# jellyFish_schematic.net
KiCad netlist of a schematic drawn in EAGLE
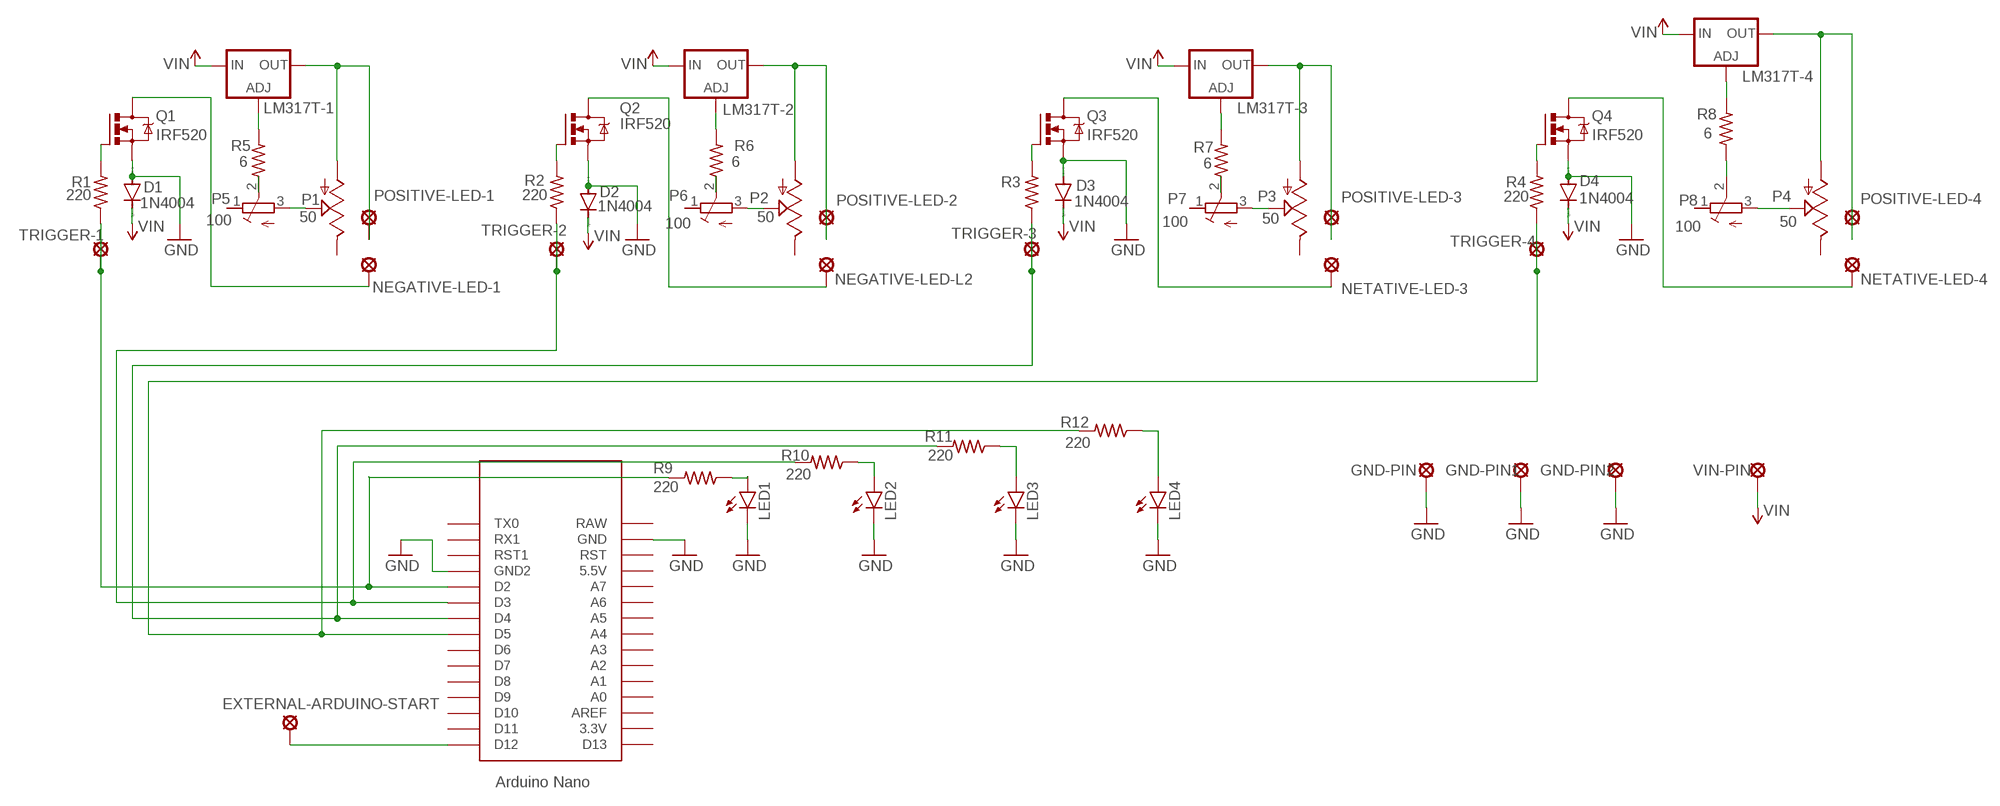
[diagram p0: schematic, sheet 1]

(export (version "E")
  (design (tool "Eeschema 10.0.6"))
  (components
    (comp (ref "D1")
      (value "1N4004")
      (footprint "eagle-import:DO41-10")
      (libsource (lib "eagle-import") (part "1N4004"))
    )
    (comp (ref "D2")
      (value "1N4004")
      (footprint "eagle-import:DO41-10")
      (libsource (lib "eagle-import") (part "1N4004"))
    )
    (comp (ref "D3")
      (value "1N4004")
      (footprint "eagle-import:DO41-10")
      (libsource (lib "eagle-import") (part "1N4004"))
    )
    (comp (ref "D4")
      (value "1N4004")
      (footprint "eagle-import:DO41-10")
      (libsource (lib "eagle-import") (part "1N4004"))
    )
    (comp (ref "EXTERNAL-ARDUINO-START")
      (value "LSP10")
      (footprint "eagle-import:LSP10")
      (libsource (lib "eagle-import") (part "LSP10"))
    )
    (comp (ref "GND-PIN")
      (value "LSP10")
      (footprint "eagle-import:LSP10")
      (libsource (lib "eagle-import") (part "LSP10"))
    )
    (comp (ref "GND-PIN1")
      (value "LSP10")
      (footprint "eagle-import:LSP10")
      (libsource (lib "eagle-import") (part "LSP10"))
    )
    (comp (ref "GND-PIN2")
      (value "LSP10")
      (footprint "eagle-import:LSP10")
      (libsource (lib "eagle-import") (part "LSP10"))
    )
    (comp (ref "LED1")
      (value "LEDCHIPLED_0805")
      (footprint "eagle-import:CHIPLED_0805")
      (libsource (lib "eagle-import") (part "LEDCHIPLED_0805"))
    )
    (comp (ref "LED2")
      (value "LEDCHIPLED_0805")
      (footprint "eagle-import:CHIPLED_0805")
      (libsource (lib "eagle-import") (part "LEDCHIPLED_0805"))
    )
    (comp (ref "LED3")
      (value "LEDCHIPLED_0805")
      (footprint "eagle-import:CHIPLED_0805")
      (libsource (lib "eagle-import") (part "LEDCHIPLED_0805"))
    )
    (comp (ref "LED4")
      (value "LEDCHIPLED_0805")
      (footprint "eagle-import:CHIPLED_0805")
      (libsource (lib "eagle-import") (part "LEDCHIPLED_0805"))
    )
    (comp (ref "LM317T-1")
      (value "LM317TS")
      (footprint "eagle-import:317TS")
      (libsource (lib "eagle-import") (part "LM317TS"))
    )
    (comp (ref "LM317T-2")
      (value "LM317TS")
      (footprint "eagle-import:317TS")
      (libsource (lib "eagle-import") (part "LM317TS"))
    )
    (comp (ref "LM317T-3")
      (value "LM317TS")
      (footprint "eagle-import:317TS")
      (libsource (lib "eagle-import") (part "LM317TS"))
    )
    (comp (ref "LM317T-4")
      (value "LM317TS")
      (footprint "eagle-import:317TS")
      (libsource (lib "eagle-import") (part "LM317TS"))
    )
    (comp (ref "NEGATIVE-LED-1")
      (value "LSP10")
      (footprint "eagle-import:LSP10")
      (libsource (lib "eagle-import") (part "LSP10"))
    )
    (comp (ref "NEGATIVE-LED-L2")
      (value "LSP10")
      (footprint "eagle-import:LSP10")
      (libsource (lib "eagle-import") (part "LSP10"))
    )
    (comp (ref "NETATIVE-LED-3")
      (value "LSP10")
      (footprint "eagle-import:LSP10")
      (libsource (lib "eagle-import") (part "LSP10"))
    )
    (comp (ref "NETATIVE-LED-4")
      (value "LSP10")
      (footprint "eagle-import:LSP10")
      (libsource (lib "eagle-import") (part "LSP10"))
    )
    (comp (ref "P1")
      (value "50")
      (footprint "eagle-import:S63P")
      (libsource (lib "eagle-import") (part "TRIM_US-S63P"))
    )
    (comp (ref "P2")
      (value "50")
      (footprint "eagle-import:S63P")
      (libsource (lib "eagle-import") (part "TRIM_US-S63P"))
    )
    (comp (ref "P3")
      (value "50")
      (footprint "eagle-import:S63P")
      (libsource (lib "eagle-import") (part "TRIM_US-S63P"))
    )
    (comp (ref "P4")
      (value "50")
      (footprint "eagle-import:S63P")
      (libsource (lib "eagle-import") (part "TRIM_US-S63P"))
    )
    (comp (ref "P5")
      (value "100")
      (footprint "eagle-import:RTRIMT93YA")
      (libsource (lib "eagle-import") (part "R-TRIMMT93YA"))
    )
    (comp (ref "P6")
      (value "100")
      (footprint "eagle-import:RTRIMT93YA")
      (libsource (lib "eagle-import") (part "R-TRIMMT93YA"))
    )
    (comp (ref "P7")
      (value "100")
      (footprint "eagle-import:RTRIMT93YA")
      (libsource (lib "eagle-import") (part "R-TRIMMT93YA"))
    )
    (comp (ref "P8")
      (value "100")
      (footprint "eagle-import:RTRIMT93YA")
      (libsource (lib "eagle-import") (part "R-TRIMMT93YA"))
    )
    (comp (ref "POSITIVE-LED-1")
      (value "POSITIVE LED")
      (footprint "eagle-import:LSP10")
      (libsource (lib "eagle-import") (part "LSP10"))
    )
    (comp (ref "POSITIVE-LED-2")
      (value "LSP10")
      (footprint "eagle-import:LSP10")
      (libsource (lib "eagle-import") (part "LSP10"))
    )
    (comp (ref "POSITIVE-LED-3")
      (value "LSP10")
      (footprint "eagle-import:LSP10")
      (libsource (lib "eagle-import") (part "LSP10"))
    )
    (comp (ref "POSITIVE-LED-4")
      (value "LSP10")
      (footprint "eagle-import:LSP10")
      (libsource (lib "eagle-import") (part "LSP10"))
    )
    (comp (ref "Q1")
      (value "IRF520")
      (footprint "eagle-import:TO220BV")
      (libsource (lib "eagle-import") (part "IRF520"))
    )
    (comp (ref "Q2")
      (value "IRF520")
      (footprint "eagle-import:TO220BV")
      (libsource (lib "eagle-import") (part "IRF520"))
    )
    (comp (ref "Q3")
      (value "IRF520")
      (footprint "eagle-import:TO220BV")
      (libsource (lib "eagle-import") (part "IRF520"))
    )
    (comp (ref "Q4")
      (value "IRF520")
      (footprint "eagle-import:TO220BV")
      (libsource (lib "eagle-import") (part "IRF520"))
    )
    (comp (ref "R1")
      (value "220")
      (footprint "eagle-import:R0805")
      (libsource (lib "eagle-import") (part "R-US_R0805"))
    )
    (comp (ref "R2")
      (value "220")
      (footprint "eagle-import:R0805")
      (libsource (lib "eagle-import") (part "R-US_R0805"))
    )
    (comp (ref "R3")
      (value "220")
      (footprint "eagle-import:R0805")
      (libsource (lib "eagle-import") (part "R-US_R0805"))
    )
    (comp (ref "R4")
      (value "220")
      (footprint "eagle-import:R0805")
      (libsource (lib "eagle-import") (part "R-US_R0805"))
    )
    (comp (ref "R5")
      (value "6")
      (footprint "eagle-import:R0805")
      (libsource (lib "eagle-import") (part "R-US_R0805"))
    )
    (comp (ref "R6")
      (value "6")
      (footprint "eagle-import:R0805")
      (libsource (lib "eagle-import") (part "R-US_R0805"))
    )
    (comp (ref "R7")
      (value "6")
      (footprint "eagle-import:R0805")
      (libsource (lib "eagle-import") (part "R-US_R0805"))
    )
    (comp (ref "R8")
      (value "6")
      (footprint "eagle-import:R0805")
      (libsource (lib "eagle-import") (part "R-US_R0805"))
    )
    (comp (ref "R9")
      (value "220")
      (footprint "eagle-import:R0805")
      (libsource (lib "eagle-import") (part "R-US_R0805"))
    )
    (comp (ref "R10")
      (value "220")
      (footprint "eagle-import:R0805")
      (libsource (lib "eagle-import") (part "R-US_R0805"))
    )
    (comp (ref "R11")
      (value "220")
      (footprint "eagle-import:R0805")
      (libsource (lib "eagle-import") (part "R-US_R0805"))
    )
    (comp (ref "R12")
      (value "220")
      (footprint "eagle-import:R0805")
      (libsource (lib "eagle-import") (part "R-US_R0805"))
    )
    (comp (ref "TRIGGER-1")
      (value "LSP10")
      (footprint "eagle-import:LSP10")
      (libsource (lib "eagle-import") (part "LSP10"))
    )
    (comp (ref "TRIGGER-2")
      (value "LSP10")
      (footprint "eagle-import:LSP10")
      (libsource (lib "eagle-import") (part "LSP10"))
    )
    (comp (ref "TRIGGER-3")
      (value "LSP10")
      (footprint "eagle-import:LSP10")
      (libsource (lib "eagle-import") (part "LSP10"))
    )
    (comp (ref "TRIGGER-4")
      (value "LSP10")
      (footprint "eagle-import:LSP10")
      (libsource (lib "eagle-import") (part "LSP10"))
    )
    (comp (ref "U$1")
      (value "NANO")
      (footprint "eagle-import:NANO")
      (libsource (lib "eagle-import") (part "NANO"))
    )
    (comp (ref "VIN-PIN")
      (value "LSP10")
      (footprint "eagle-import:LSP10")
      (libsource (lib "eagle-import") (part "LSP10"))
    )
  )
  (nets
    (net (code "1") (name "GND") (class "Default")
      (node (ref "D1") (pin "A") (pinfunction "A_A") (pintype "passive"))
      (node (ref "D2") (pin "A") (pinfunction "A_A") (pintype "passive"))
      (node (ref "D3") (pin "A") (pinfunction "A_A") (pintype "passive"))
      (node (ref "D4") (pin "A") (pinfunction "A_A") (pintype "passive"))
      (node (ref "GND-PIN") (pin "MP") (pinfunction "MP_MP") (pintype "passive"))
      (node (ref "GND-PIN1") (pin "MP") (pinfunction "MP_MP") (pintype "passive"))
      (node (ref "GND-PIN2") (pin "MP") (pinfunction "MP_MP") (pintype "passive"))
      (node (ref "LED1") (pin "C") (pinfunction "C_C") (pintype "passive"))
      (node (ref "LED2") (pin "C") (pinfunction "C_C") (pintype "passive"))
      (node (ref "LED3") (pin "C") (pinfunction "C_C") (pintype "passive"))
      (node (ref "LED4") (pin "C") (pinfunction "C_C") (pintype "passive"))
      (node (ref "Q1") (pin "S") (pinfunction "S_S") (pintype "passive"))
      (node (ref "Q2") (pin "S") (pinfunction "S_S") (pintype "passive"))
      (node (ref "Q3") (pin "S") (pinfunction "S_S") (pintype "passive"))
      (node (ref "Q4") (pin "S") (pinfunction "S_S") (pintype "passive"))
      (node (ref "U$1") (pin "GND") (pinfunction "GND_GND") (pintype "bidirectional"))
      (node (ref "U$1") (pin "GND1") (pinfunction "GND2_GND1") (pintype "bidirectional"))
    )
    (net (code "2") (name "Net-(EXTERNAL-ARDUINO-START-PadMP)") (class "Default")
      (node (ref "EXTERNAL-ARDUINO-START") (pin "MP") (pinfunction "MP_MP") (pintype "passive"))
      (node (ref "U$1") (pin "D12") (pinfunction "D12_D12") (pintype "bidirectional"))
    )
    (net (code "3") (name "Net-(LED1-PadA)") (class "Default")
      (node (ref "LED1") (pin "A") (pinfunction "A_A") (pintype "passive"))
      (node (ref "R9") (pin "1") (pinfunction "1_1") (pintype "passive"))
    )
    (net (code "4") (name "Net-(LED2-PadA)") (class "Default")
      (node (ref "LED2") (pin "A") (pinfunction "A_A") (pintype "passive"))
      (node (ref "R10") (pin "1") (pinfunction "1_1") (pintype "passive"))
    )
    (net (code "5") (name "Net-(LED3-PadA)") (class "Default")
      (node (ref "LED3") (pin "A") (pinfunction "A_A") (pintype "passive"))
      (node (ref "R11") (pin "1") (pinfunction "1_1") (pintype "passive"))
    )
    (net (code "6") (name "Net-(LED4-PadA)") (class "Default")
      (node (ref "LED4") (pin "A") (pinfunction "A_A") (pintype "passive"))
      (node (ref "R12") (pin "1") (pinfunction "1_1") (pintype "passive"))
    )
    (net (code "7") (name "Net-(LM317T-1-ADJ)") (class "Default")
      (node (ref "LM317T-1") (pin "1") (pinfunction "ADJ_1") (pintype "input"))
      (node (ref "R5") (pin "2") (pinfunction "2_2") (pintype "passive"))
    )
    (net (code "8") (name "Net-(LM317T-1-OUT)") (class "Default")
      (node (ref "LM317T-1") (pin "2") (pinfunction "OUT_2") (pintype "passive"))
      (node (ref "P1") (pin "A") (pinfunction "A_A") (pintype "passive"))
      (node (ref "POSITIVE-LED-1") (pin "MP") (pinfunction "MP_MP") (pintype "passive"))
    )
    (net (code "9") (name "Net-(LM317T-2-ADJ)") (class "Default")
      (node (ref "LM317T-2") (pin "1") (pinfunction "ADJ_1") (pintype "input"))
      (node (ref "R6") (pin "2") (pinfunction "2_2") (pintype "passive"))
    )
    (net (code "10") (name "Net-(LM317T-2-OUT)") (class "Default")
      (node (ref "LM317T-2") (pin "2") (pinfunction "OUT_2") (pintype "passive"))
      (node (ref "P2") (pin "A") (pinfunction "A_A") (pintype "passive"))
      (node (ref "POSITIVE-LED-2") (pin "MP") (pinfunction "MP_MP") (pintype "passive"))
    )
    (net (code "11") (name "Net-(LM317T-3-ADJ)") (class "Default")
      (node (ref "LM317T-3") (pin "1") (pinfunction "ADJ_1") (pintype "input"))
      (node (ref "R7") (pin "2") (pinfunction "2_2") (pintype "passive"))
    )
    (net (code "12") (name "Net-(LM317T-3-OUT)") (class "Default")
      (node (ref "LM317T-3") (pin "2") (pinfunction "OUT_2") (pintype "passive"))
      (node (ref "P3") (pin "A") (pinfunction "A_A") (pintype "passive"))
      (node (ref "POSITIVE-LED-3") (pin "MP") (pinfunction "MP_MP") (pintype "passive"))
    )
    (net (code "13") (name "Net-(LM317T-4-ADJ)") (class "Default")
      (node (ref "LM317T-4") (pin "1") (pinfunction "ADJ_1") (pintype "input"))
      (node (ref "R8") (pin "2") (pinfunction "2_2") (pintype "passive"))
    )
    (net (code "14") (name "Net-(LM317T-4-OUT)") (class "Default")
      (node (ref "LM317T-4") (pin "2") (pinfunction "OUT_2") (pintype "passive"))
      (node (ref "P4") (pin "A") (pinfunction "A_A") (pintype "passive"))
      (node (ref "POSITIVE-LED-4") (pin "MP") (pinfunction "MP_MP") (pintype "passive"))
    )
    (net (code "15") (name "Net-(NEGATIVE-LED-1-PadMP)") (class "Default")
      (node (ref "NEGATIVE-LED-1") (pin "MP") (pinfunction "MP_MP") (pintype "passive"))
      (node (ref "Q1") (pin "D") (pinfunction "D_D") (pintype "passive"))
    )
    (net (code "16") (name "Net-(NEGATIVE-LED-L2-PadMP)") (class "Default")
      (node (ref "NEGATIVE-LED-L2") (pin "MP") (pinfunction "MP_MP") (pintype "passive"))
      (node (ref "Q2") (pin "D") (pinfunction "D_D") (pintype "passive"))
    )
    (net (code "17") (name "Net-(NETATIVE-LED-3-PadMP)") (class "Default")
      (node (ref "NETATIVE-LED-3") (pin "MP") (pinfunction "MP_MP") (pintype "passive"))
      (node (ref "Q3") (pin "D") (pinfunction "D_D") (pintype "passive"))
    )
    (net (code "18") (name "Net-(NETATIVE-LED-4-PadMP)") (class "Default")
      (node (ref "NETATIVE-LED-4") (pin "MP") (pinfunction "MP_MP") (pintype "passive"))
      (node (ref "Q4") (pin "D") (pinfunction "D_D") (pintype "passive"))
    )
    (net (code "19") (name "Net-(P5-A)") (class "Default")
      (node (ref "P1") (pin "S") (pinfunction "S_S") (pintype "passive"))
      (node (ref "P5") (pin "3") (pinfunction "A_3") (pintype "passive"))
    )
    (net (code "20") (name "Net-(P5-S)") (class "Default")
      (node (ref "P5") (pin "2") (pinfunction "S_2") (pintype "passive"))
      (node (ref "R5") (pin "1") (pinfunction "1_1") (pintype "passive"))
    )
    (net (code "21") (name "Net-(P6-A)") (class "Default")
      (node (ref "P2") (pin "S") (pinfunction "S_S") (pintype "passive"))
      (node (ref "P6") (pin "3") (pinfunction "A_3") (pintype "passive"))
    )
    (net (code "22") (name "Net-(P6-S)") (class "Default")
      (node (ref "P6") (pin "2") (pinfunction "S_2") (pintype "passive"))
      (node (ref "R6") (pin "1") (pinfunction "1_1") (pintype "passive"))
    )
    (net (code "23") (name "Net-(P7-A)") (class "Default")
      (node (ref "P3") (pin "S") (pinfunction "S_S") (pintype "passive"))
      (node (ref "P7") (pin "3") (pinfunction "A_3") (pintype "passive"))
    )
    (net (code "24") (name "Net-(P7-S)") (class "Default")
      (node (ref "P7") (pin "2") (pinfunction "S_2") (pintype "passive"))
      (node (ref "R7") (pin "1") (pinfunction "1_1") (pintype "passive"))
    )
    (net (code "25") (name "Net-(P8-A)") (class "Default")
      (node (ref "P4") (pin "S") (pinfunction "S_S") (pintype "passive"))
      (node (ref "P8") (pin "3") (pinfunction "A_3") (pintype "passive"))
    )
    (net (code "26") (name "Net-(P8-S)") (class "Default")
      (node (ref "P8") (pin "2") (pinfunction "S_2") (pintype "passive"))
      (node (ref "R8") (pin "1") (pinfunction "1_1") (pintype "passive"))
    )
    (net (code "27") (name "Net-(Q1-PadG)") (class "Default")
      (node (ref "Q1") (pin "G") (pinfunction "G_G") (pintype "passive"))
      (node (ref "R1") (pin "2") (pinfunction "2_2") (pintype "passive"))
    )
    (net (code "28") (name "Net-(Q2-PadG)") (class "Default")
      (node (ref "Q2") (pin "G") (pinfunction "G_G") (pintype "passive"))
      (node (ref "R2") (pin "2") (pinfunction "2_2") (pintype "passive"))
    )
    (net (code "29") (name "Net-(Q3-PadG)") (class "Default")
      (node (ref "Q3") (pin "G") (pinfunction "G_G") (pintype "passive"))
      (node (ref "R3") (pin "2") (pinfunction "2_2") (pintype "passive"))
    )
    (net (code "30") (name "Net-(Q4-PadG)") (class "Default")
      (node (ref "Q4") (pin "G") (pinfunction "G_G") (pintype "passive"))
      (node (ref "R4") (pin "2") (pinfunction "2_2") (pintype "passive"))
    )
    (net (code "31") (name "Net-(R1-Pad1)") (class "Default")
      (node (ref "R1") (pin "1") (pinfunction "1_1") (pintype "passive"))
      (node (ref "R9") (pin "2") (pinfunction "2_2") (pintype "passive"))
      (node (ref "TRIGGER-1") (pin "MP") (pinfunction "MP_MP") (pintype "passive"))
      (node (ref "U$1") (pin "D2") (pinfunction "D2_D2") (pintype "bidirectional"))
    )
    (net (code "32") (name "Net-(R10-Pad2)") (class "Default")
      (node (ref "R10") (pin "2") (pinfunction "2_2") (pintype "passive"))
      (node (ref "R2") (pin "1") (pinfunction "1_1") (pintype "passive"))
      (node (ref "TRIGGER-2") (pin "MP") (pinfunction "MP_MP") (pintype "passive"))
      (node (ref "U$1") (pin "D3") (pinfunction "D3_D3") (pintype "bidirectional"))
    )
    (net (code "33") (name "Net-(R11-Pad2)") (class "Default")
      (node (ref "R11") (pin "2") (pinfunction "2_2") (pintype "passive"))
      (node (ref "R3") (pin "1") (pinfunction "1_1") (pintype "passive"))
      (node (ref "TRIGGER-3") (pin "MP") (pinfunction "MP_MP") (pintype "passive"))
      (node (ref "U$1") (pin "D4") (pinfunction "D4_D4") (pintype "bidirectional"))
    )
    (net (code "34") (name "Net-(R12-Pad2)") (class "Default")
      (node (ref "R12") (pin "2") (pinfunction "2_2") (pintype "passive"))
      (node (ref "R4") (pin "1") (pinfunction "1_1") (pintype "passive"))
      (node (ref "TRIGGER-4") (pin "MP") (pinfunction "MP_MP") (pintype "passive"))
      (node (ref "U$1") (pin "D5") (pinfunction "D5_D5") (pintype "bidirectional"))
    )
    (net (code "35") (name "VIN") (class "Default")
      (node (ref "D1") (pin "C") (pinfunction "C_C") (pintype "passive"))
      (node (ref "D2") (pin "C") (pinfunction "C_C") (pintype "passive"))
      (node (ref "D3") (pin "C") (pinfunction "C_C") (pintype "passive"))
      (node (ref "D4") (pin "C") (pinfunction "C_C") (pintype "passive"))
      (node (ref "LM317T-1") (pin "3") (pinfunction "IN_3") (pintype "input"))
      (node (ref "LM317T-2") (pin "3") (pinfunction "IN_3") (pintype "input"))
      (node (ref "LM317T-3") (pin "3") (pinfunction "IN_3") (pintype "input"))
      (node (ref "LM317T-4") (pin "3") (pinfunction "IN_3") (pintype "input"))
      (node (ref "VIN-PIN") (pin "MP") (pinfunction "MP_MP") (pintype "passive"))
    )
    (net (code "36") (name "unconnected-(P1-PadE)") (class "Default")
      (node (ref "P1") (pin "E") (pinfunction "E_E") (pintype "passive"))
    )
    (net (code "37") (name "unconnected-(P2-PadE)") (class "Default")
      (node (ref "P2") (pin "E") (pinfunction "E_E") (pintype "passive"))
    )
    (net (code "38") (name "unconnected-(P3-PadE)") (class "Default")
      (node (ref "P3") (pin "E") (pinfunction "E_E") (pintype "passive"))
    )
    (net (code "39") (name "unconnected-(P4-PadE)") (class "Default")
      (node (ref "P4") (pin "E") (pinfunction "E_E") (pintype "passive"))
    )
    (net (code "40") (name "unconnected-(P5-E-Pad1)") (class "Default")
      (node (ref "P5") (pin "1") (pinfunction "E_1") (pintype "passive"))
    )
    (net (code "41") (name "unconnected-(P6-E-Pad1)") (class "Default")
      (node (ref "P6") (pin "1") (pinfunction "E_1") (pintype "passive"))
    )
    (net (code "42") (name "unconnected-(P7-E-Pad1)") (class "Default")
      (node (ref "P7") (pin "1") (pinfunction "E_1") (pintype "passive"))
    )
    (net (code "43") (name "unconnected-(P8-E-Pad1)") (class "Default")
      (node (ref "P8") (pin "1") (pinfunction "E_1") (pintype "passive"))
    )
    (net (code "44") (name "unconnected-(U$1-5.5V-Pad5V)") (class "Default")
      (node (ref "U$1") (pin "5V") (pinfunction "5.5V_5V") (pintype "bidirectional"))
    )
    (net (code "45") (name "unconnected-(U$1-Pad3.3V)") (class "Default")
      (node (ref "U$1") (pin "3.3V") (pinfunction "3.3V_3.3V") (pintype "bidirectional"))
    )
    (net (code "46") (name "unconnected-(U$1-PadA0)") (class "Default")
      (node (ref "U$1") (pin "A0") (pinfunction "A0_A0") (pintype "bidirectional"))
    )
    (net (code "47") (name "unconnected-(U$1-PadA1)") (class "Default")
      (node (ref "U$1") (pin "A1") (pinfunction "A1_A1") (pintype "bidirectional"))
    )
    (net (code "48") (name "unconnected-(U$1-PadA2)") (class "Default")
      (node (ref "U$1") (pin "A2") (pinfunction "A2_A2") (pintype "bidirectional"))
    )
    (net (code "49") (name "unconnected-(U$1-PadA3)") (class "Default")
      (node (ref "U$1") (pin "A3") (pinfunction "A3_A3") (pintype "bidirectional"))
    )
    (net (code "50") (name "unconnected-(U$1-PadA4)") (class "Default")
      (node (ref "U$1") (pin "A4") (pinfunction "A4_A4") (pintype "bidirectional"))
    )
    (net (code "51") (name "unconnected-(U$1-PadA5)") (class "Default")
      (node (ref "U$1") (pin "A5") (pinfunction "A5_A5") (pintype "bidirectional"))
    )
    (net (code "52") (name "unconnected-(U$1-PadA6)") (class "Default")
      (node (ref "U$1") (pin "A6") (pinfunction "A6_A6") (pintype "bidirectional"))
    )
    (net (code "53") (name "unconnected-(U$1-PadA7)") (class "Default")
      (node (ref "U$1") (pin "A7") (pinfunction "A7_A7") (pintype "bidirectional"))
    )
    (net (code "54") (name "unconnected-(U$1-PadAREF)") (class "Default")
      (node (ref "U$1") (pin "AREF") (pinfunction "AREF_AREF") (pintype "bidirectional"))
    )
    (net (code "55") (name "unconnected-(U$1-PadD6)") (class "Default")
      (node (ref "U$1") (pin "D6") (pinfunction "D6_D6") (pintype "bidirectional"))
    )
    (net (code "56") (name "unconnected-(U$1-PadD7)") (class "Default")
      (node (ref "U$1") (pin "D7") (pinfunction "D7_D7") (pintype "bidirectional"))
    )
    (net (code "57") (name "unconnected-(U$1-PadD8)") (class "Default")
      (node (ref "U$1") (pin "D8") (pinfunction "D8_D8") (pintype "bidirectional"))
    )
    (net (code "58") (name "unconnected-(U$1-PadD9)") (class "Default")
      (node (ref "U$1") (pin "D9") (pinfunction "D9_D9") (pintype "bidirectional"))
    )
    (net (code "59") (name "unconnected-(U$1-PadD10)") (class "Default")
      (node (ref "U$1") (pin "D10") (pinfunction "D10_D10") (pintype "bidirectional"))
    )
    (net (code "60") (name "unconnected-(U$1-PadD11)") (class "Default")
      (node (ref "U$1") (pin "D11") (pinfunction "D11_D11") (pintype "bidirectional"))
    )
    (net (code "61") (name "unconnected-(U$1-PadD13)") (class "Default")
      (node (ref "U$1") (pin "D13") (pinfunction "D13_D13") (pintype "bidirectional"))
    )
    (net (code "62") (name "unconnected-(U$1-PadICSP1)") (class "Default")
      (node (ref "U$1") (pin "ICSP1") (pinfunction "ICSP1_ICSP1") (pintype "bidirectional"))
    )
    (net (code "63") (name "unconnected-(U$1-PadICSP2)") (class "Default")
      (node (ref "U$1") (pin "ICSP2") (pinfunction "ICSP2_ICSP2") (pintype "bidirectional"))
    )
    (net (code "64") (name "unconnected-(U$1-PadICSP3)") (class "Default")
      (node (ref "U$1") (pin "ICSP3") (pinfunction "ICSP3_ICSP3") (pintype "bidirectional"))
    )
    (net (code "65") (name "unconnected-(U$1-PadICSP4)") (class "Default")
      (node (ref "U$1") (pin "ICSP4") (pinfunction "ICSP4_ICSP4") (pintype "bidirectional"))
    )
    (net (code "66") (name "unconnected-(U$1-PadICSP5)") (class "Default")
      (node (ref "U$1") (pin "ICSP5") (pinfunction "ICSP5_ICSP5") (pintype "bidirectional"))
    )
    (net (code "67") (name "unconnected-(U$1-PadICSP6)") (class "Default")
      (node (ref "U$1") (pin "ICSP6") (pinfunction "ICSP6_ICSP6") (pintype "bidirectional"))
    )
    (net (code "68") (name "unconnected-(U$1-PadRAW)") (class "Default")
      (node (ref "U$1") (pin "RAW") (pinfunction "RAW_RAW") (pintype "bidirectional"))
    )
    (net (code "69") (name "unconnected-(U$1-PadRST)") (class "Default")
      (node (ref "U$1") (pin "RST") (pinfunction "RST_RST") (pintype "bidirectional"))
    )
    (net (code "70") (name "unconnected-(U$1-PadRST1)") (class "Default")
      (node (ref "U$1") (pin "RST1") (pinfunction "RST1_RST1") (pintype "bidirectional"))
    )
    (net (code "71") (name "unconnected-(U$1-PadRX1)") (class "Default")
      (node (ref "U$1") (pin "RX1") (pinfunction "RX1_RX1") (pintype "bidirectional"))
    )
    (net (code "72") (name "unconnected-(U$1-PadTX0)") (class "Default")
      (node (ref "U$1") (pin "TX0") (pinfunction "TX0_TX0") (pintype "bidirectional"))
    )
  )
)
